# Sheet2.net
KiCad netlist of a schematic drawn in Altium Designer
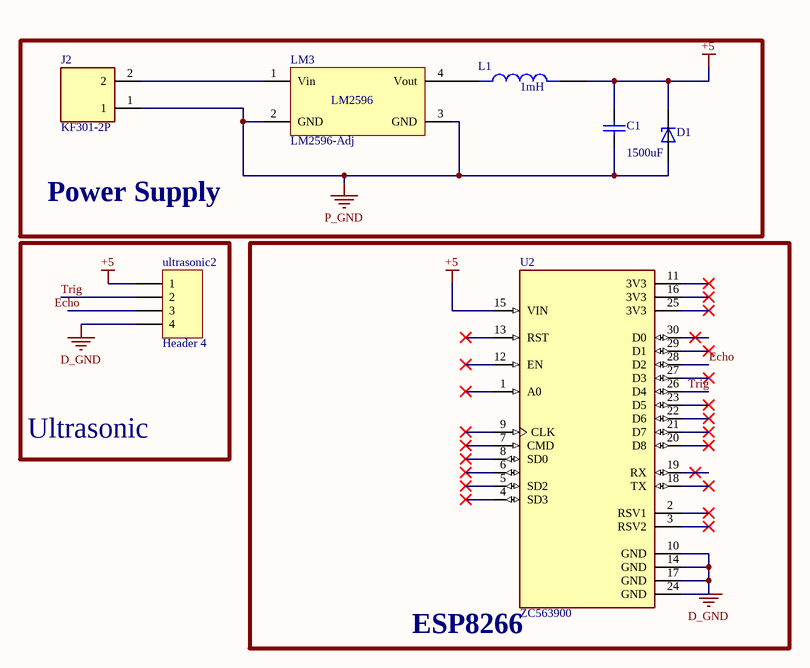
[diagram p0: Sheet2.SchDoc]

(export (version "E")
  (design (tool "Eeschema 10.0.6"))
  (components
    (comp (ref "C1")
      (value "1500uF")
      (footprint "RAD-0.3")
      (description "Capacitor")
      (fields (field (name "Comment") "Cap") (field (name "PUBLISHER") "Altium Limited"))
      (libsource (lib "Miscellaneous+Devices") (part "Cap"))
    )
    (comp (ref "D1")
      (value "P6KE6.8A")
      (footprint "DIOAD1300W80L670D310")
      (description "10.5V Clamp 58.1A Ipp Tvs Diode Through Hole DO-204AC (DO-15)")
      (fields (field (name "MF") "Littelfuse Inc."))
      (libsource (lib "P6KE6.8A") (part "P6KE6.8A"))
    )
    (comp (ref "J2")
      (value "KF301-2P")
      (footprint "HANDSON_KF301-2P")
      (description "2 Pin Terminal Block 5mm Pitch")
      (fields (field (name "MF") "Handson Technology"))
      (libsource (lib "KF301-2P") (part "KF301-2P"))
    )
    (comp (ref "L1")
      (value "1mH")
      (footprint "INDAD1680W80L1200D650")
      (description "470 ÂµH Unshielded Wirewound Inductor 510 mA 1.9Ohm Max Axial")
      (fields (field (name "MF") "EPCOS") (field (name "MP") "B82145A1474J000"))
      (libsource (lib "B82145A1474J000") (part "B82145A1474J000"))
    )
    (comp (ref "LM3")
      (value "LM2596-Adj")
      (footprint "lm2596")
      (description "Designed By @Alixahedi")
      (libsource (lib "LM2596-Adj") (part "LM2596-Adj"))
    )
    (comp (ref "U2")
      (value "ZC563900")
      (footprint "MODULE_ZC563900")
      (description "NodeMcu Lua ESP8266 WIFI Internet of Things Network Development Module Board")
      (fields (field (name "MF") "YKS"))
      (libsource (lib "ZC563900 (1)") (part "ZC563900"))
    )
    (comp (ref "ultrasonic2")
      (value "Header 4")
      (footprint "HDR1X4")
      (description "Header, 4-Pin")
      (fields (field (name "PUBLISHER") "Altium Limited"))
      (libsource (lib "Miscellaneous+Connectors") (part "Header 4"))
    )
  )
  (nets
    (net (code "1") (name "+5") (class "Default")
      (node (ref "C1") (pin "2") (pinfunction "2_2") (pintype "passive"))
      (node (ref "D1") (pin "C") (pinfunction "C_C") (pintype "passive"))
      (node (ref "L1") (pin "2") (pinfunction "2_2") (pintype "passive"))
      (node (ref "U2") (pin "15") (pinfunction "VIN_15") (pintype "input"))
      (node (ref "ultrasonic2") (pin "1") (pinfunction "1_1") (pintype "passive"))
    )
    (net (code "2") (name "/Echo") (class "Default")
      (node (ref "U2") (pin "28") (pinfunction "D2_28") (pintype "bidirectional"))
      (node (ref "ultrasonic2") (pin "3") (pinfunction "3_3") (pintype "passive"))
    )
    (net (code "3") (name "/Trig") (class "Default")
      (node (ref "U2") (pin "26") (pinfunction "D4_26") (pintype "bidirectional"))
      (node (ref "ultrasonic2") (pin "2") (pinfunction "2_2") (pintype "passive"))
    )
    (net (code "4") (name "D_GND") (class "Default")
      (node (ref "U2") (pin "10") (pinfunction "GND_10") (pintype "power_in"))
      (node (ref "U2") (pin "14") (pinfunction "GND_14") (pintype "power_in"))
      (node (ref "U2") (pin "17") (pinfunction "GND_17") (pintype "power_in"))
      (node (ref "U2") (pin "24") (pinfunction "GND_24") (pintype "power_in"))
      (node (ref "ultrasonic2") (pin "4") (pinfunction "4_4") (pintype "passive"))
    )
    (net (code "5") (name "Net-(LM3-Vin)") (class "Default")
      (node (ref "J2") (pin "2") (pinfunction "2_2") (pintype "passive"))
      (node (ref "LM3") (pin "1") (pinfunction "Vin_1") (pintype "passive"))
    )
    (net (code "6") (name "Net-(LM3-Vout)") (class "Default")
      (node (ref "L1") (pin "1") (pinfunction "1_1") (pintype "passive"))
      (node (ref "LM3") (pin "4") (pinfunction "Vout_4") (pintype "passive"))
    )
    (net (code "7") (name "P_GND") (class "Default")
      (node (ref "C1") (pin "1") (pinfunction "1_1") (pintype "passive"))
      (node (ref "D1") (pin "A") (pinfunction "A_A") (pintype "passive"))
      (node (ref "J2") (pin "1") (pinfunction "1_1") (pintype "passive"))
      (node (ref "LM3") (pin "2") (pinfunction "GND_2") (pintype "passive"))
      (node (ref "LM3") (pin "3") (pinfunction "GND_3") (pintype "passive"))
    )
    (net (code "8") (name "unconnected-(U2-3V3-Pad11)") (class "Default")
      (node (ref "U2") (pin "11") (pinfunction "3V3_11") (pintype "power_in+no_connect"))
    )
    (net (code "9") (name "unconnected-(U2-3V3-Pad16)") (class "Default")
      (node (ref "U2") (pin "16") (pinfunction "3V3_16") (pintype "power_in+no_connect"))
    )
    (net (code "10") (name "unconnected-(U2-3V3-Pad25)") (class "Default")
      (node (ref "U2") (pin "25") (pinfunction "3V3_25") (pintype "power_in+no_connect"))
    )
    (net (code "11") (name "unconnected-(U2-A0-Pad1)") (class "Default")
      (node (ref "U2") (pin "1") (pinfunction "A0_1") (pintype "input+no_connect"))
    )
    (net (code "12") (name "unconnected-(U2-CLK-Pad9)") (class "Default")
      (node (ref "U2") (pin "9") (pinfunction "CLK_9") (pintype "input+no_connect"))
    )
    (net (code "13") (name "unconnected-(U2-CMD-Pad7)") (class "Default")
      (node (ref "U2") (pin "7") (pinfunction "CMD_7") (pintype "input+no_connect"))
    )
    (net (code "14") (name "unconnected-(U2-D0-Pad30)") (class "Default")
      (node (ref "U2") (pin "30") (pinfunction "D0_30") (pintype "bidirectional"))
    )
    (net (code "15") (name "unconnected-(U2-D1-Pad29)") (class "Default")
      (node (ref "U2") (pin "29") (pinfunction "D1_29") (pintype "bidirectional+no_connect"))
    )
    (net (code "16") (name "unconnected-(U2-D3-Pad27)") (class "Default")
      (node (ref "U2") (pin "27") (pinfunction "D3_27") (pintype "bidirectional+no_connect"))
    )
    (net (code "17") (name "unconnected-(U2-D5-Pad23)") (class "Default")
      (node (ref "U2") (pin "23") (pinfunction "D5_23") (pintype "bidirectional+no_connect"))
    )
    (net (code "18") (name "unconnected-(U2-D6-Pad22)") (class "Default")
      (node (ref "U2") (pin "22") (pinfunction "D6_22") (pintype "bidirectional+no_connect"))
    )
    (net (code "19") (name "unconnected-(U2-D7-Pad21)") (class "Default")
      (node (ref "U2") (pin "21") (pinfunction "D7_21") (pintype "bidirectional+no_connect"))
    )
    (net (code "20") (name "unconnected-(U2-D8-Pad20)") (class "Default")
      (node (ref "U2") (pin "20") (pinfunction "D8_20") (pintype "bidirectional+no_connect"))
    )
    (net (code "21") (name "unconnected-(U2-EN-Pad12)") (class "Default")
      (node (ref "U2") (pin "12") (pinfunction "EN_12") (pintype "input+no_connect"))
    )
    (net (code "22") (name "unconnected-(U2-RST-Pad13)") (class "Default")
      (node (ref "U2") (pin "13") (pinfunction "RST_13") (pintype "input+no_connect"))
    )
    (net (code "23") (name "unconnected-(U2-RSV1-Pad2)") (class "Default")
      (node (ref "U2") (pin "2") (pinfunction "RSV1_2") (pintype "passive+no_connect"))
    )
    (net (code "24") (name "unconnected-(U2-RSV2-Pad3)") (class "Default")
      (node (ref "U2") (pin "3") (pinfunction "RSV2_3") (pintype "passive+no_connect"))
    )
    (net (code "25") (name "unconnected-(U2-RX-Pad19)") (class "Default")
      (node (ref "U2") (pin "19") (pinfunction "RX_19") (pintype "bidirectional"))
    )
    (net (code "26") (name "unconnected-(U2-SD0-Pad8)") (class "Default")
      (node (ref "U2") (pin "8") (pinfunction "SD0_8") (pintype "bidirectional+no_connect"))
    )
    (net (code "27") (name "unconnected-(U2-SD1-Pad6)") (class "Default")
      (node (ref "U2") (pin "6") (pinfunction "SD1_6") (pintype "bidirectional+no_connect"))
    )
    (net (code "28") (name "unconnected-(U2-SD2-Pad5)") (class "Default")
      (node (ref "U2") (pin "5") (pinfunction "SD2_5") (pintype "bidirectional+no_connect"))
    )
    (net (code "29") (name "unconnected-(U2-SD3-Pad4)") (class "Default")
      (node (ref "U2") (pin "4") (pinfunction "SD3_4") (pintype "bidirectional+no_connect"))
    )
    (net (code "30") (name "unconnected-(U2-TX-Pad18)") (class "Default")
      (node (ref "U2") (pin "18") (pinfunction "TX_18") (pintype "bidirectional+no_connect"))
    )
  )
)
